# 2021-02-22_22-45-18.net
KiCad netlist of a schematic drawn in EAGLE
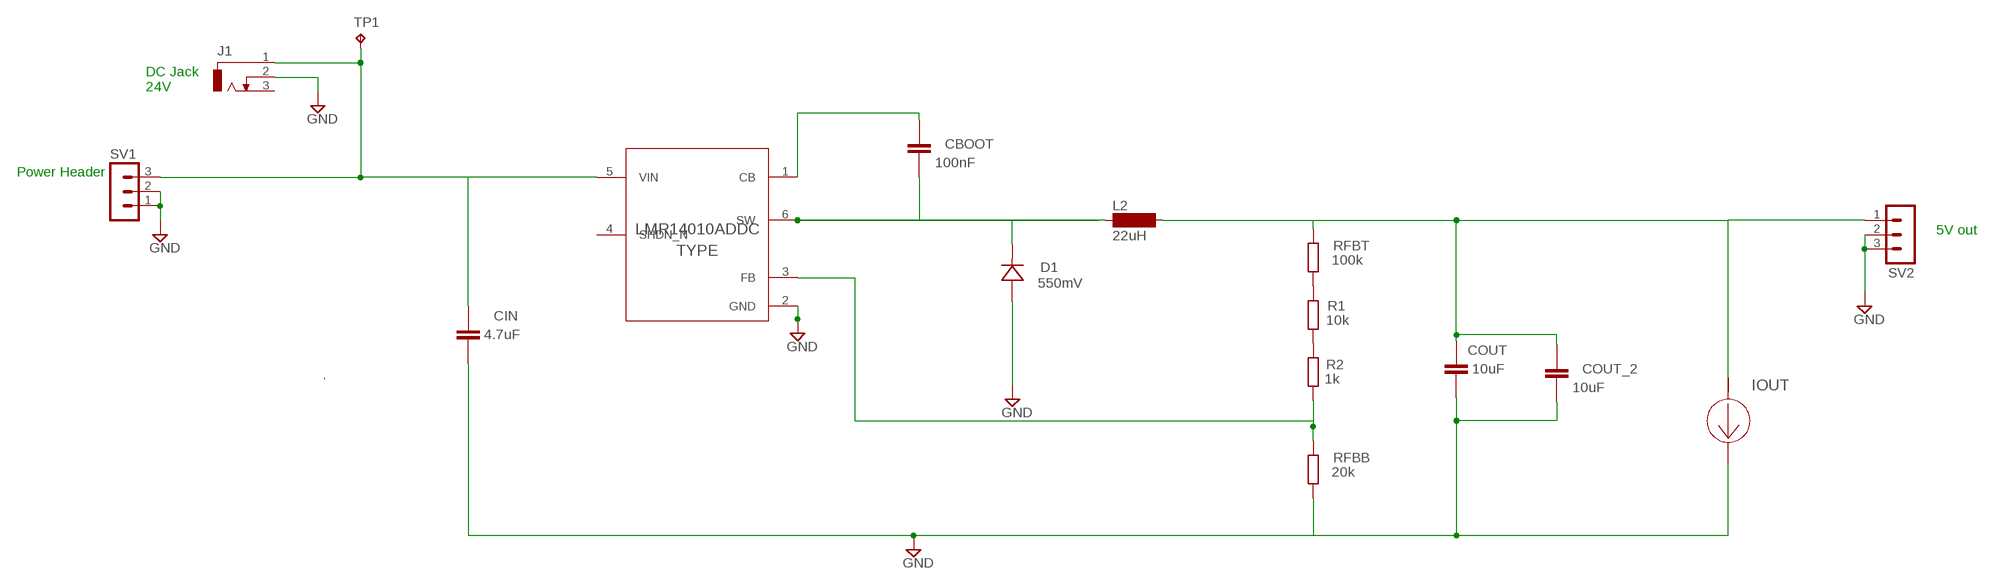
[diagram p0: schematic, sheet 1]

(export (version "E")
  (design (tool "Eeschema 10.0.6"))
  (components
    (comp (ref "CBOOT")
      (value "100nF")
      (footprint "eagle-import:C0603")
      (libsource (lib "eagle-import") (part "CAPACITOR-0603"))
    )
    (comp (ref "CIN")
      (value "4.7uF")
      (footprint "eagle-import:C0603")
      (libsource (lib "eagle-import") (part "CAPACITOR-0603"))
    )
    (comp (ref "COUT")
      (value "10uF")
      (footprint "eagle-import:C0603")
      (libsource (lib "eagle-import") (part "CAPACITOR-0603"))
    )
    (comp (ref "COUT_2")
      (value "10uF")
      (footprint "eagle-import:C0603")
      (libsource (lib "eagle-import") (part "CAPACITOR-0603"))
    )
    (comp (ref "D1")
      (value "550mV")
      (footprint "eagle-import:DFN0603-2")
      (libsource (lib "eagle-import") (part "DIODE-DFN0603-2"))
    )
    (comp (ref "IOUT")
      (value "WB_CURRENT_LOAD")
      (footprint "eagle-import:WB_CURRENT_LOAD")
      (libsource (lib "eagle-import") (part "WB_CURRENT_LOADWB_CURRENT_LOAD"))
    )
    (comp (ref "J1")
      (value "DCJ0303")
      (footprint "eagle-import:DCJ0303")
      (libsource (lib "eagle-import") (part "DCJ0303"))
    )
    (comp (ref "L2")
      (value "22uH")
      (footprint "eagle-import:SD8")
      (libsource (lib "eagle-import") (part "SD8"))
    )
    (comp (ref "LMR14010ADDC")
      (value "LMR14010ADDCR")
      (footprint "eagle-import:DDC0006A_N")
      (fields (field (name "MANUFACTURER") "Texas Instruments") (field (name "TYPE") "TYPE"))
      (libsource (lib "eagle-import") (part "LMR14010ADDCRLMR14010ADDCR"))
    )
    (comp (ref "R1")
      (value "10k")
      (footprint "eagle-import:R0603")
      (libsource (lib "eagle-import") (part "RESISTOR-0603"))
    )
    (comp (ref "R2")
      (value "1k")
      (footprint "eagle-import:R0603")
      (libsource (lib "eagle-import") (part "RESISTOR-0603"))
    )
    (comp (ref "RFBB")
      (value "20k")
      (footprint "eagle-import:R0603")
      (libsource (lib "eagle-import") (part "RESISTOR-0603"))
    )
    (comp (ref "RFBT")
      (value "100k")
      (footprint "eagle-import:R0603")
      (libsource (lib "eagle-import") (part "RESISTOR-0603"))
    )
    (comp (ref "SV1")
      (value "MA03-1")
      (footprint "eagle-import:MA03-1")
      (libsource (lib "eagle-import") (part "MA03-1"))
    )
    (comp (ref "SV2")
      (value "MA03-1")
      (footprint "eagle-import:MA03-1")
      (libsource (lib "eagle-import") (part "MA03-1"))
    )
    (comp (ref "TP1")
      (value "TPPAD1-13")
      (footprint "eagle-import:P1-13")
      (libsource (lib "eagle-import") (part "TPPAD1-13"))
    )
  )
  (nets
    (net (code "1") (name "/2") (class "Default")
      (node (ref "LMR14010ADDC") (pin "3") (pinfunction "FB_3") (pintype "input"))
      (node (ref "R2") (pin "1") (pinfunction "1_1") (pintype "passive"))
      (node (ref "RFBB") (pin "2") (pinfunction "2_2") (pintype "passive"))
    )
    (net (code "2") (name "/5") (class "Default")
      (node (ref "COUT") (pin "2") (pinfunction "2_2") (pintype "passive"))
      (node (ref "COUT_2") (pin "2") (pinfunction "2_2") (pintype "passive"))
      (node (ref "IOUT") (pin "1") (pinfunction "+_1") (pintype "passive"))
      (node (ref "L2") (pin "2") (pinfunction "2_2") (pintype "passive"))
      (node (ref "RFBT") (pin "2") (pinfunction "2_2") (pintype "passive"))
      (node (ref "SV2") (pin "1") (pinfunction "1_1") (pintype "passive"))
    )
    (net (code "3") (name "/6") (class "Default")
      (node (ref "CBOOT") (pin "1") (pinfunction "1_1") (pintype "passive"))
      (node (ref "D1") (pin "C") (pinfunction "C_C") (pintype "passive"))
    )
    (net (code "4") (name "GND") (class "Default")
      (node (ref "CIN") (pin "1") (pinfunction "1_1") (pintype "passive"))
      (node (ref "COUT") (pin "1") (pinfunction "1_1") (pintype "passive"))
      (node (ref "COUT_2") (pin "1") (pinfunction "1_1") (pintype "passive"))
      (node (ref "D1") (pin "A") (pinfunction "A_A") (pintype "passive"))
      (node (ref "IOUT") (pin "2") (pinfunction "-_2") (pintype "passive"))
      (node (ref "J1") (pin "2") (pinfunction "2_2") (pintype "passive"))
      (node (ref "LMR14010ADDC") (pin "2") (pinfunction "GND_2") (pintype "power_in"))
      (node (ref "SV1") (pin "1") (pinfunction "1_1") (pintype "passive"))
      (node (ref "SV1") (pin "2") (pinfunction "2_2") (pintype "passive"))
      (node (ref "SV2") (pin "2") (pinfunction "2_2") (pintype "passive"))
      (node (ref "SV2") (pin "3") (pinfunction "3_3") (pintype "passive"))
    )
    (net (code "5") (name "Net-(LMR14010ADDC-CB)") (class "Default")
      (node (ref "CBOOT") (pin "2") (pinfunction "2_2") (pintype "passive"))
      (node (ref "LMR14010ADDC") (pin "1") (pinfunction "CB_1") (pintype "passive"))
    )
    (net (code "6") (name "Net-(LMR14010ADDC-SW)") (class "Default")
      (node (ref "L2") (pin "1") (pinfunction "1_1") (pintype "passive"))
      (node (ref "LMR14010ADDC") (pin "6") (pinfunction "SW_6") (pintype "power_in"))
    )
    (net (code "7") (name "Net-(LMR14010ADDC-VIN)") (class "Default")
      (node (ref "CIN") (pin "2") (pinfunction "2_2") (pintype "passive"))
      (node (ref "J1") (pin "1") (pinfunction "1_1") (pintype "passive"))
      (node (ref "LMR14010ADDC") (pin "5") (pinfunction "VIN_5") (pintype "power_in"))
      (node (ref "SV1") (pin "3") (pinfunction "3_3") (pintype "passive"))
      (node (ref "TP1") (pin "TP") (pinfunction "TP_TP") (pintype "input"))
    )
    (net (code "8") (name "Net-(R1-Pad1)") (class "Default")
      (node (ref "R1") (pin "1") (pinfunction "1_1") (pintype "passive"))
      (node (ref "R2") (pin "2") (pinfunction "2_2") (pintype "passive"))
    )
    (net (code "9") (name "Net-(R1-Pad2)") (class "Default")
      (node (ref "R1") (pin "2") (pinfunction "2_2") (pintype "passive"))
      (node (ref "RFBT") (pin "1") (pinfunction "1_1") (pintype "passive"))
    )
    (net (code "10") (name "unconnected-(J1-Pad3)") (class "Default")
      (node (ref "J1") (pin "3") (pinfunction "3_3") (pintype "passive"))
    )
    (net (code "11") (name "unconnected-(LMR14010ADDC-SHDN_N-Pad4)") (class "Default")
      (node (ref "LMR14010ADDC") (pin "4") (pinfunction "SHDN_N_4") (pintype "input"))
    )
    (net (code "12") (name "unconnected-(RFBB-Pad1)") (class "Default")
      (node (ref "RFBB") (pin "1") (pinfunction "1_1") (pintype "passive"))
    )
  )
)
